# CAN_Interface.net
KiCad netlist of a schematic drawn in Altium Designer
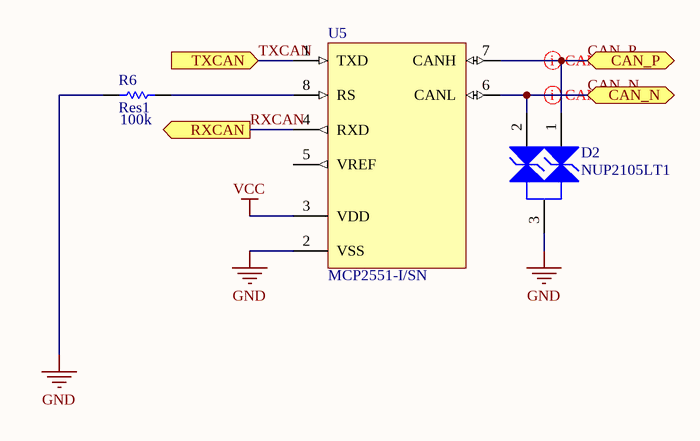
[diagram p0: CAN_Interface.SchDoc]

(export (version "E")
  (design (tool "Eeschema 10.0.6"))
  (components
    (comp (ref "D2")
      (value "NUP2105LT1")
      (footprint "ONSC-SOT-23-3-318-08_V")
      (description "Dual Line CAN Bus Protector, 3-Pin SOT-23, Tape and Reel")
      (fields (field (name "MANUFACTURER") "On Semiconductor"))
      (libsource (lib "Altium Content Vault") (part "ONSC-NUP21X5X-SOT-23-3-318-08"))
    )
    (comp (ref "R6")
      (value "Res1")
      (footprint "6-0805_L")
      (description "Resistor")
      (fields (field (name "ALTIUM_VALUE") "100k") (field (name "PUBLISHER") "Altium Limited"))
      (libsource (lib "Miscellaneous Devices") (part "Res1"))
    )
    (comp (ref "U5")
      (value "MCP2551-I/SN")
      (footprint "SOIC-SN8_N")
      (description "High-Speed CAN Transceiver, 8-Pin SOIC, Industrial Temperature")
      (libsource (lib "Altium Content Vault") (part "COM-TRX-MCP2551-8"))
    )
  )
  (nets
    (net (code "1") (name "/CAN_N") (class "Default")
      (node (ref "D2") (pin "2") (pinfunction "K_2") (pintype "passive"))
      (node (ref "U5") (pin "6") (pinfunction "CANL_6") (pintype "bidirectional"))
    )
    (net (code "2") (name "/CAN_P") (class "Default")
      (node (ref "D2") (pin "1") (pinfunction "K_1") (pintype "passive"))
      (node (ref "U5") (pin "7") (pinfunction "CANH_7") (pintype "bidirectional"))
    )
    (net (code "3") (name "/RXCAN") (class "Default")
      (node (ref "U5") (pin "4") (pinfunction "RXD_4") (pintype "output"))
    )
    (net (code "4") (name "/TXCAN") (class "Default")
      (node (ref "U5") (pin "1") (pinfunction "TXD_1") (pintype "input"))
    )
    (net (code "5") (name "GND") (class "Default")
      (node (ref "D2") (pin "3") (pinfunction "K_3") (pintype "passive"))
      (node (ref "R6") (pin "1") (pinfunction "1_1") (pintype "passive"))
      (node (ref "U5") (pin "2") (pinfunction "VSS_2") (pintype "power_in"))
    )
    (net (code "6") (name "Net-(U5-RS)") (class "Default")
      (node (ref "R6") (pin "2") (pinfunction "2_2") (pintype "passive"))
      (node (ref "U5") (pin "8") (pinfunction "RS_8") (pintype "input"))
    )
    (net (code "7") (name "VCC") (class "Default")
      (node (ref "U5") (pin "3") (pinfunction "VDD_3") (pintype "power_in"))
    )
    (net (code "8") (name "unconnected-(U5-VREF-Pad5)") (class "Default")
      (node (ref "U5") (pin "5") (pinfunction "VREF_5") (pintype "output"))
    )
  )
)
